# Camera.net
KiCad netlist of a schematic drawn in Altium Designer
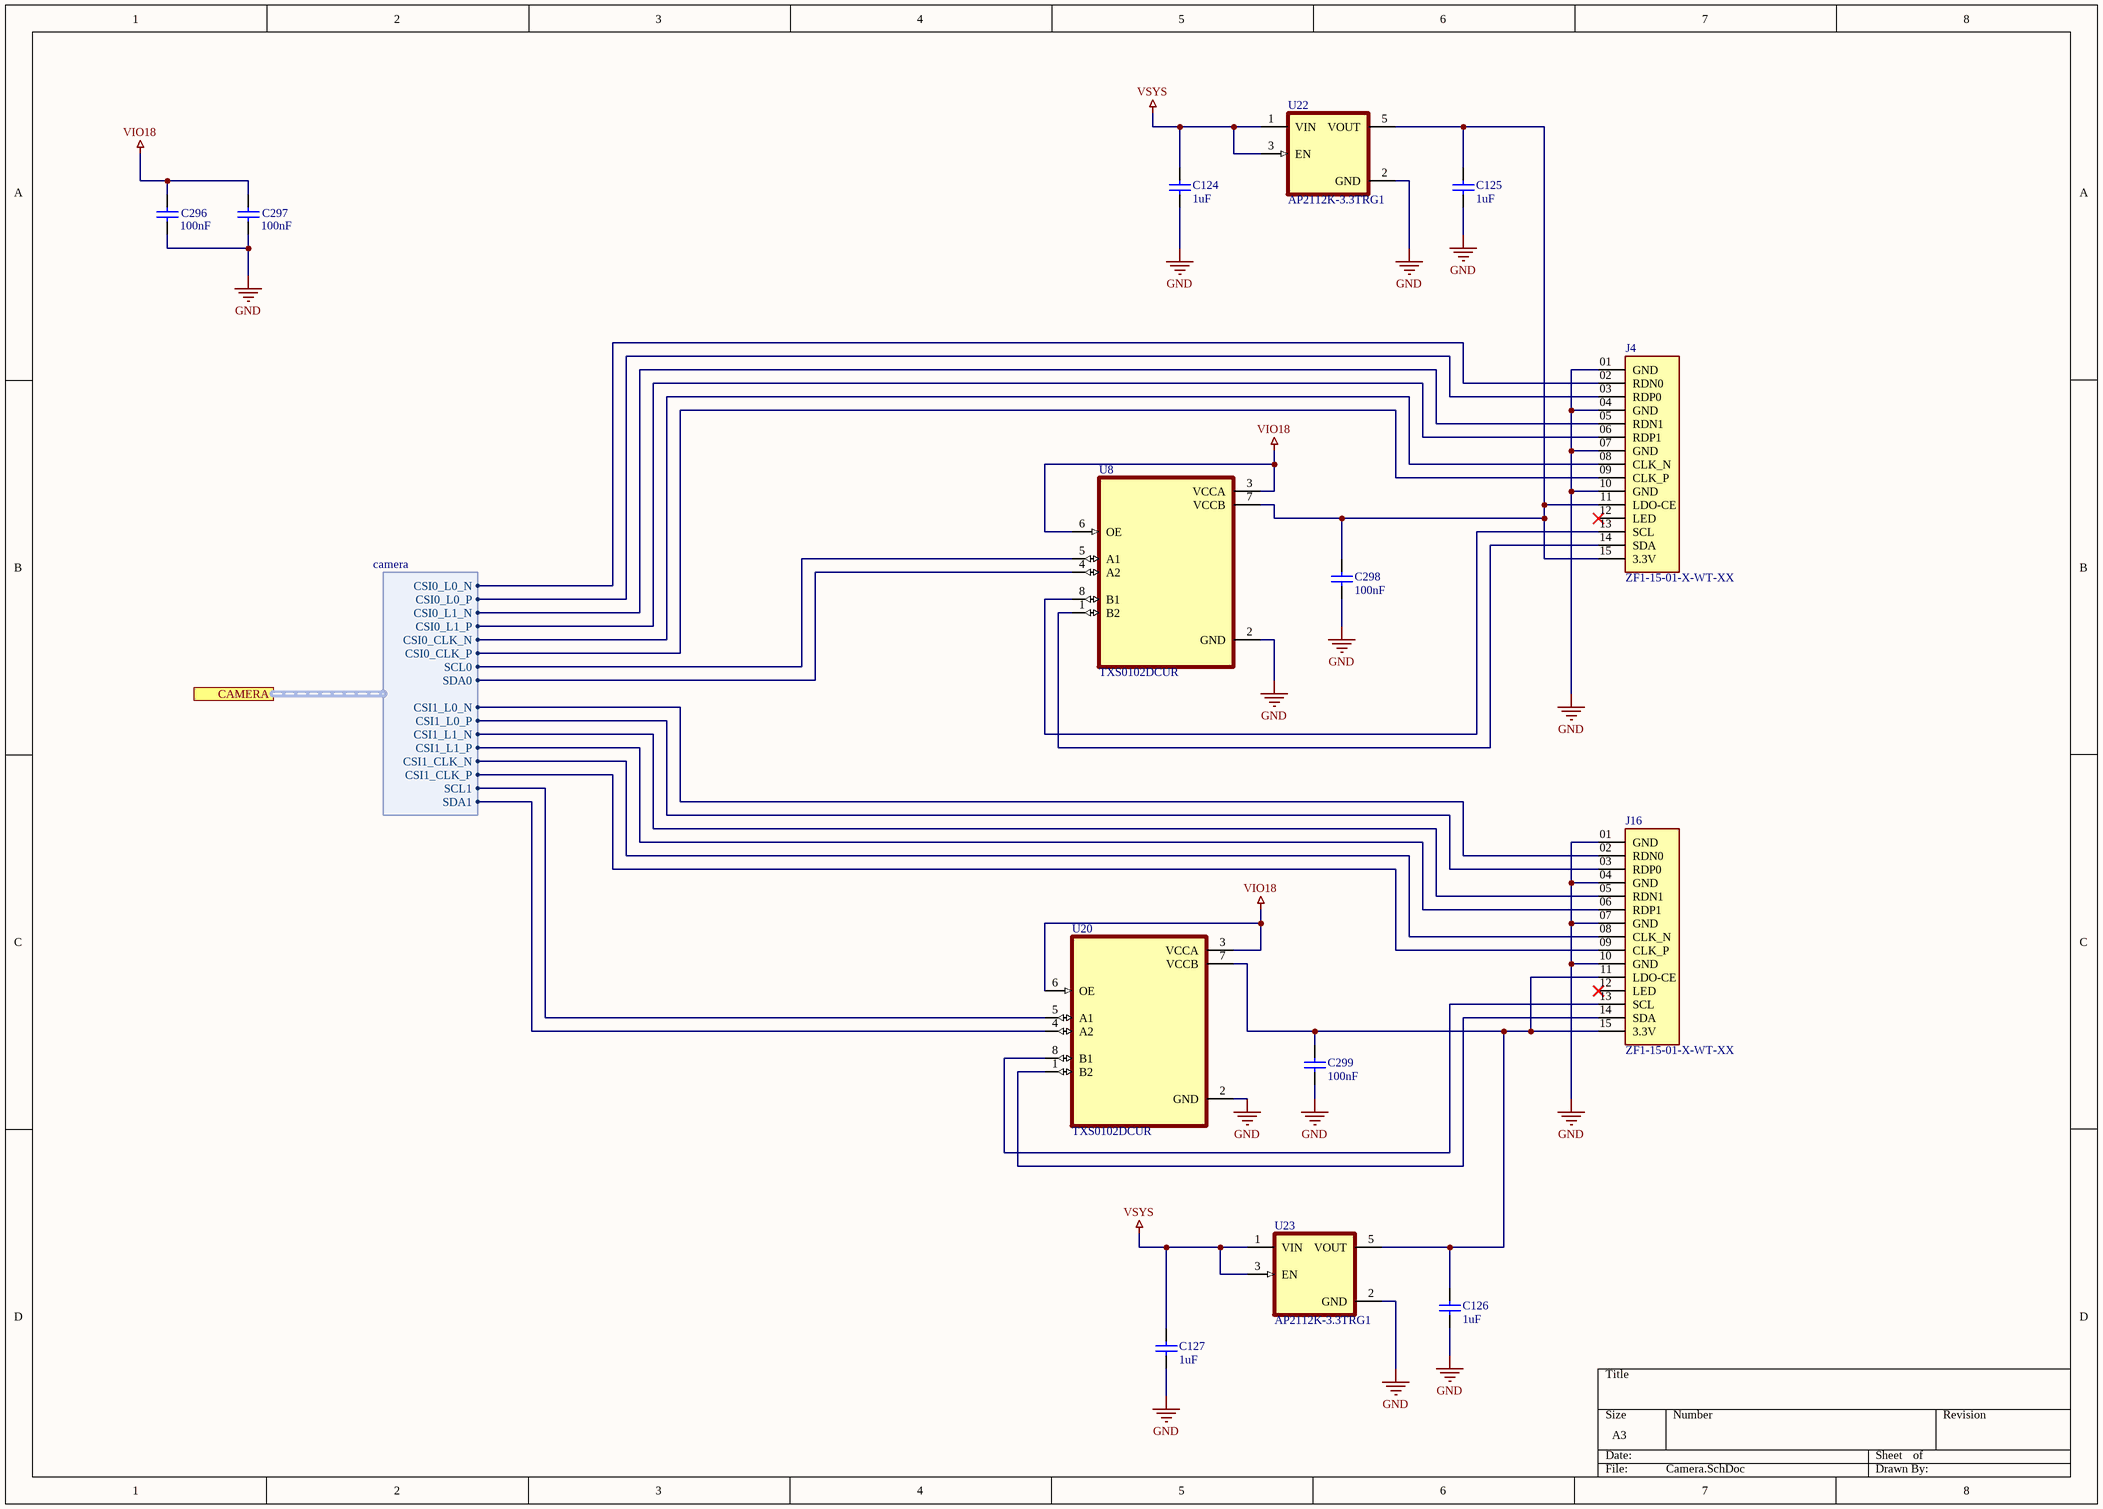
[diagram p0: Camera.SchDoc]

(export (version "E")
  (design (tool "Eeschema 10.0.6"))
  (components
    (comp (ref "C124")
      (value "1uF")
      (footprint "C0805")
      (fields (field (name "Comment") "C0805"))
      (libsource (lib "kit") (part "C0805"))
    )
    (comp (ref "C125")
      (value "1uF")
      (footprint "C0805")
      (fields (field (name "Comment") "C0805"))
      (libsource (lib "kit") (part "C0805"))
    )
    (comp (ref "C126")
      (value "1uF")
      (footprint "C0805")
      (fields (field (name "Comment") "C0805"))
      (libsource (lib "kit") (part "C0805"))
    )
    (comp (ref "C127")
      (value "1uF")
      (footprint "C0805")
      (fields (field (name "Comment") "C0805"))
      (libsource (lib "kit") (part "C0805"))
    )
    (comp (ref "C296")
      (value "100nF")
      (footprint "C0603")
      (fields (field (name "Comment") "C0603"))
      (libsource (lib "kit") (part "C0603"))
    )
    (comp (ref "C297")
      (value "100nF")
      (footprint "C0603")
      (fields (field (name "Comment") "C0603"))
      (libsource (lib "kit") (part "C0603"))
    )
    (comp (ref "C298")
      (value "100nF")
      (footprint "C0603")
      (fields (field (name "Comment") "C0603"))
      (libsource (lib "kit") (part "C0603"))
    )
    (comp (ref "C299")
      (value "100nF")
      (footprint "C0603")
      (fields (field (name "Comment") "C0603"))
      (libsource (lib "kit") (part "C0603"))
    )
    (comp (ref "J4")
      (value "ZF1-15-01-X-WT-XX")
      (footprint "SAMTEC_ZF1-15-01-X-WT-XX")
      (libsource (lib "kit") (part "ZF1-15-01-X-WT-XX"))
    )
    (comp (ref "J16")
      (value "ZF1-15-01-X-WT-XX")
      (footprint "SAMTEC_ZF1-15-01-X-WT-XX")
      (libsource (lib "kit") (part "ZF1-15-01-X-WT-XX"))
    )
    (comp (ref "U8")
      (value "TXS0102DCUR")
      (footprint "SOP50P310X90-8N")
      (libsource (lib "kit") (part "TXS0102DCUR"))
    )
    (comp (ref "U20")
      (value "TXS0102DCUR")
      (footprint "SOP50P310X90-8N")
      (libsource (lib "kit") (part "TXS0102DCUR"))
    )
    (comp (ref "U22")
      (value "AP2112K-3.3TRG1")
      (footprint "SOT95P285X140-5N")
      (description "Linear Voltage Regulator IC Positive Fixed 1 Output 600mA SOT-25")
      (libsource (lib "kit") (part "AP2112K-3.3TRG1"))
    )
    (comp (ref "U23")
      (value "AP2112K-3.3TRG1")
      (footprint "SOT95P285X140-5N")
      (description "Linear Voltage Regulator IC Positive Fixed 1 Output 600mA SOT-25")
      (libsource (lib "kit") (part "AP2112K-3.3TRG1"))
    )
  )
  (nets
    (net (code "2") (name "/CSI0_CLK_N") (class "Default")
      (node (ref "J4") (pin "08") (pinfunction "CLK_N_08") (pintype "passive"))
    )
    (net (code "3") (name "/CSI0_CLK_P") (class "Default")
      (node (ref "J4") (pin "09") (pinfunction "CLK_P_09") (pintype "passive"))
    )
    (net (code "4") (name "/CSI0_L0_N") (class "Default")
      (node (ref "J4") (pin "02") (pinfunction "RDN0_02") (pintype "passive"))
    )
    (net (code "5") (name "/CSI0_L0_P") (class "Default")
      (node (ref "J4") (pin "03") (pinfunction "RDP0_03") (pintype "passive"))
    )
    (net (code "6") (name "/CSI0_L1_N") (class "Default")
      (node (ref "J4") (pin "05") (pinfunction "RDN1_05") (pintype "passive"))
    )
    (net (code "7") (name "/CSI0_L1_P") (class "Default")
      (node (ref "J4") (pin "06") (pinfunction "RDP1_06") (pintype "passive"))
    )
    (net (code "8") (name "/CSI1_CLK_N") (class "Default")
      (node (ref "J16") (pin "08") (pinfunction "CLK_N_08") (pintype "passive"))
    )
    (net (code "9") (name "/CSI1_CLK_P") (class "Default")
      (node (ref "J16") (pin "09") (pinfunction "CLK_P_09") (pintype "passive"))
    )
    (net (code "10") (name "/CSI1_L0_N") (class "Default")
      (node (ref "J16") (pin "02") (pinfunction "RDN0_02") (pintype "passive"))
    )
    (net (code "11") (name "/CSI1_L0_P") (class "Default")
      (node (ref "J16") (pin "03") (pinfunction "RDP0_03") (pintype "passive"))
    )
    (net (code "12") (name "/CSI1_L1_N") (class "Default")
      (node (ref "J16") (pin "05") (pinfunction "RDN1_05") (pintype "passive"))
    )
    (net (code "13") (name "/CSI1_L1_P") (class "Default")
      (node (ref "J16") (pin "06") (pinfunction "RDP1_06") (pintype "passive"))
    )
    (net (code "14") (name "/SCL0") (class "Default")
      (node (ref "U8") (pin "5") (pinfunction "A1_5") (pintype "bidirectional"))
    )
    (net (code "15") (name "/SCL1") (class "Default")
      (node (ref "U20") (pin "5") (pinfunction "A1_5") (pintype "bidirectional"))
    )
    (net (code "16") (name "/SDA0") (class "Default")
      (node (ref "U8") (pin "4") (pinfunction "A2_4") (pintype "bidirectional"))
    )
    (net (code "17") (name "/SDA1") (class "Default")
      (node (ref "U20") (pin "4") (pinfunction "A2_4") (pintype "bidirectional"))
    )
    (net (code "19") (name "GND") (class "Default")
      (node (ref "C124") (pin "1") (pinfunction "1_1") (pintype "passive"))
      (node (ref "C125") (pin "1") (pinfunction "1_1") (pintype "passive"))
      (node (ref "C126") (pin "1") (pinfunction "1_1") (pintype "passive"))
      (node (ref "C127") (pin "1") (pinfunction "1_1") (pintype "passive"))
      (node (ref "C296") (pin "1") (pinfunction "1_1") (pintype "passive"))
      (node (ref "C297") (pin "1") (pinfunction "1_1") (pintype "passive"))
      (node (ref "C298") (pin "1") (pinfunction "1_1") (pintype "passive"))
      (node (ref "C299") (pin "1") (pinfunction "1_1") (pintype "passive"))
      (node (ref "J16") (pin "01") (pinfunction "GND_01") (pintype "passive"))
      (node (ref "J16") (pin "04") (pinfunction "GND_04") (pintype "passive"))
      (node (ref "J16") (pin "07") (pinfunction "GND_07") (pintype "passive"))
      (node (ref "J16") (pin "10") (pinfunction "GND_10") (pintype "passive"))
      (node (ref "J4") (pin "01") (pinfunction "GND_01") (pintype "passive"))
      (node (ref "J4") (pin "04") (pinfunction "GND_04") (pintype "passive"))
      (node (ref "J4") (pin "07") (pinfunction "GND_07") (pintype "passive"))
      (node (ref "J4") (pin "10") (pinfunction "GND_10") (pintype "passive"))
      (node (ref "U20") (pin "2") (pinfunction "GND_2") (pintype "power_in"))
      (node (ref "U22") (pin "2") (pinfunction "GND_2") (pintype "power_in"))
      (node (ref "U23") (pin "2") (pinfunction "GND_2") (pintype "power_in"))
      (node (ref "U8") (pin "2") (pinfunction "GND_2") (pintype "power_in"))
    )
    (net (code "20") (name "Net-(J4-3.3V)") (class "Default")
      (node (ref "C125") (pin "2") (pinfunction "2_2") (pintype "passive"))
      (node (ref "C298") (pin "2") (pinfunction "2_2") (pintype "passive"))
      (node (ref "J4") (pin "11") (pinfunction "LDO-CE_11") (pintype "passive"))
      (node (ref "J4") (pin "15") (pinfunction "3.3V_15") (pintype "passive"))
      (node (ref "U22") (pin "5") (pinfunction "VOUT_5") (pintype "power_in"))
      (node (ref "U8") (pin "7") (pinfunction "VCCB_7") (pintype "power_in"))
    )
    (net (code "21") (name "Net-(J4-SCL)") (class "Default")
      (node (ref "J4") (pin "13") (pinfunction "SCL_13") (pintype "passive"))
      (node (ref "U8") (pin "8") (pinfunction "B1_8") (pintype "bidirectional"))
    )
    (net (code "22") (name "Net-(J4-SDA)") (class "Default")
      (node (ref "J4") (pin "14") (pinfunction "SDA_14") (pintype "passive"))
      (node (ref "U8") (pin "1") (pinfunction "B2_1") (pintype "bidirectional"))
    )
    (net (code "23") (name "Net-(J16-3.3V)") (class "Default")
      (node (ref "C126") (pin "2") (pinfunction "2_2") (pintype "passive"))
      (node (ref "C299") (pin "2") (pinfunction "2_2") (pintype "passive"))
      (node (ref "J16") (pin "11") (pinfunction "LDO-CE_11") (pintype "passive"))
      (node (ref "J16") (pin "15") (pinfunction "3.3V_15") (pintype "passive"))
      (node (ref "U20") (pin "7") (pinfunction "VCCB_7") (pintype "power_in"))
      (node (ref "U23") (pin "5") (pinfunction "VOUT_5") (pintype "power_in"))
    )
    (net (code "24") (name "Net-(J16-SCL)") (class "Default")
      (node (ref "J16") (pin "13") (pinfunction "SCL_13") (pintype "passive"))
      (node (ref "U20") (pin "8") (pinfunction "B1_8") (pintype "bidirectional"))
    )
    (net (code "25") (name "Net-(J16-SDA)") (class "Default")
      (node (ref "J16") (pin "14") (pinfunction "SDA_14") (pintype "passive"))
      (node (ref "U20") (pin "1") (pinfunction "B2_1") (pintype "bidirectional"))
    )
    (net (code "26") (name "VIO18") (class "Default")
      (node (ref "C296") (pin "2") (pinfunction "2_2") (pintype "passive"))
      (node (ref "C297") (pin "2") (pinfunction "2_2") (pintype "passive"))
      (node (ref "U20") (pin "3") (pinfunction "VCCA_3") (pintype "power_in"))
      (node (ref "U20") (pin "6") (pinfunction "OE_6") (pintype "input"))
      (node (ref "U8") (pin "3") (pinfunction "VCCA_3") (pintype "power_in"))
      (node (ref "U8") (pin "6") (pinfunction "OE_6") (pintype "input"))
    )
    (net (code "27") (name "VSYS") (class "Default")
      (node (ref "C124") (pin "2") (pinfunction "2_2") (pintype "passive"))
      (node (ref "C127") (pin "2") (pinfunction "2_2") (pintype "passive"))
      (node (ref "U22") (pin "1") (pinfunction "VIN_1") (pintype "power_in"))
      (node (ref "U22") (pin "3") (pinfunction "EN_3") (pintype "input"))
      (node (ref "U23") (pin "1") (pinfunction "VIN_1") (pintype "power_in"))
      (node (ref "U23") (pin "3") (pinfunction "EN_3") (pintype "input"))
    )
    (net (code "28") (name "unconnected-(J4-LED-Pad12)") (class "Default")
      (node (ref "J4") (pin "12") (pinfunction "LED_12") (pintype "passive+no_connect"))
    )
    (net (code "29") (name "unconnected-(J16-LED-Pad12)") (class "Default")
      (node (ref "J16") (pin "12") (pinfunction "LED_12") (pintype "passive+no_connect"))
    )
  )
)
